# TAH_Relay_and_Sensor_Shield.net
KiCad netlist of a schematic drawn in EAGLE
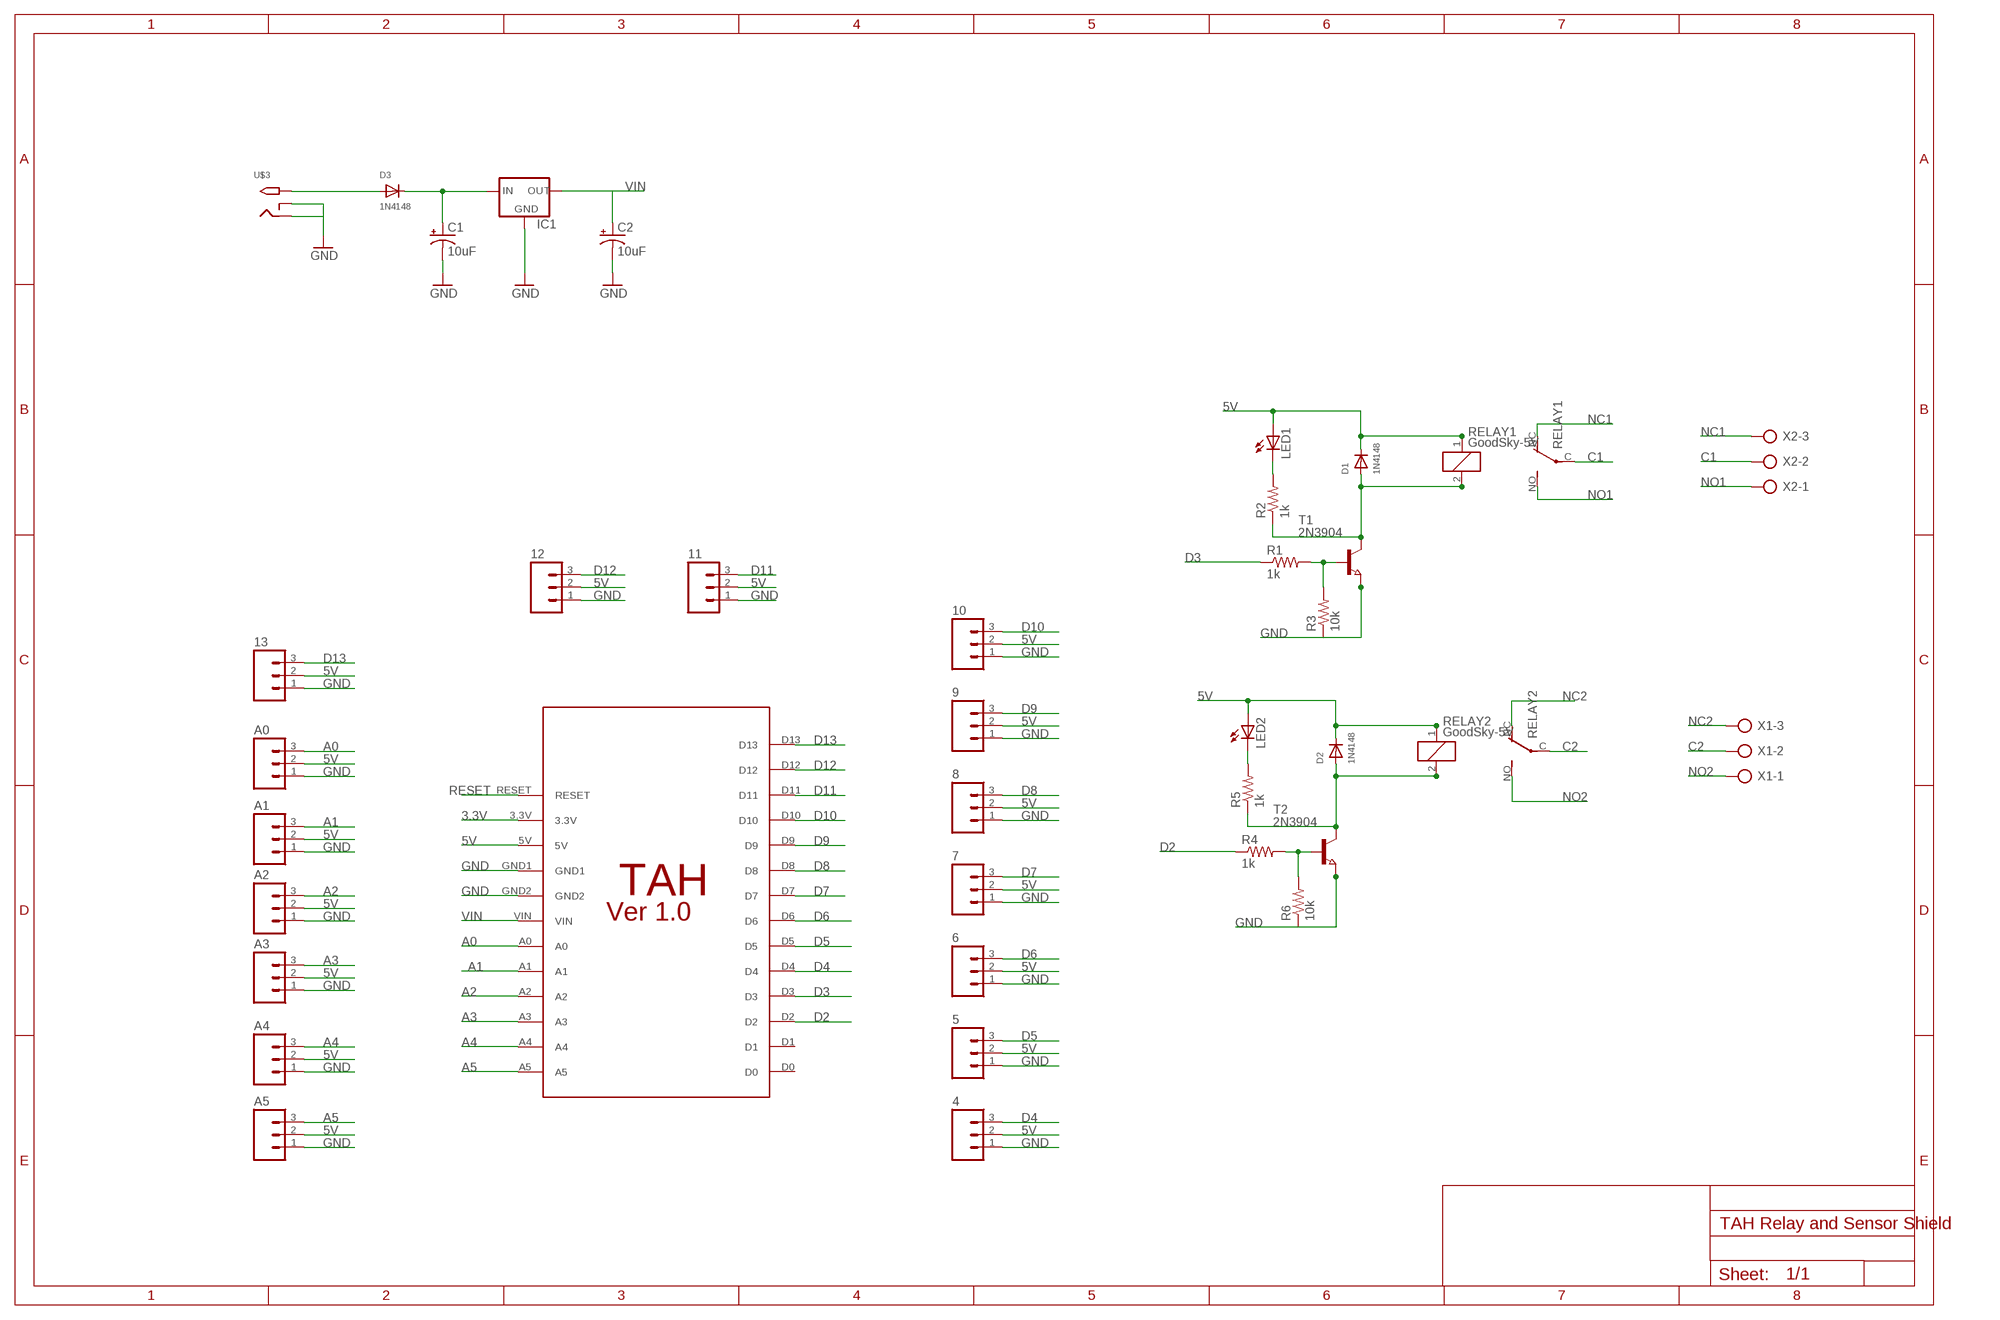
[diagram p0: schematic, sheet 1]

(export (version "E")
  (design (tool "Eeschema 10.0.6"))
  (components
    (comp (ref "4")
      (value "M03POLAR")
      (footprint "eagle-import:MOLEX-1X3")
      (libsource (lib "eagle-import") (part "M03POLAR"))
    )
    (comp (ref "5")
      (value "M03POLAR")
      (footprint "eagle-import:MOLEX-1X3")
      (libsource (lib "eagle-import") (part "M03POLAR"))
    )
    (comp (ref "6")
      (value "M03POLAR")
      (footprint "eagle-import:MOLEX-1X3")
      (libsource (lib "eagle-import") (part "M03POLAR"))
    )
    (comp (ref "7")
      (value "M03POLAR")
      (footprint "eagle-import:MOLEX-1X3")
      (libsource (lib "eagle-import") (part "M03POLAR"))
    )
    (comp (ref "8")
      (value "M03POLAR")
      (footprint "eagle-import:MOLEX-1X3")
      (libsource (lib "eagle-import") (part "M03POLAR"))
    )
    (comp (ref "9")
      (value "M03POLAR")
      (footprint "eagle-import:MOLEX-1X3")
      (libsource (lib "eagle-import") (part "M03POLAR"))
    )
    (comp (ref "10")
      (value "M03POLAR")
      (footprint "eagle-import:MOLEX-1X3")
      (libsource (lib "eagle-import") (part "M03POLAR"))
    )
    (comp (ref "11")
      (value "M03POLAR")
      (footprint "eagle-import:MOLEX-1X3")
      (libsource (lib "eagle-import") (part "M03POLAR"))
    )
    (comp (ref "12")
      (value "M03POLAR")
      (footprint "eagle-import:MOLEX-1X3")
      (libsource (lib "eagle-import") (part "M03POLAR"))
    )
    (comp (ref "13")
      (value "M03POLAR")
      (footprint "eagle-import:MOLEX-1X3")
      (libsource (lib "eagle-import") (part "M03POLAR"))
    )
    (comp (ref "A0")
      (value "M03POLAR")
      (footprint "eagle-import:MOLEX-1X3")
      (libsource (lib "eagle-import") (part "M03POLAR"))
    )
    (comp (ref "A1")
      (value "M03POLAR")
      (footprint "eagle-import:MOLEX-1X3")
      (libsource (lib "eagle-import") (part "M03POLAR"))
    )
    (comp (ref "A2")
      (value "M03POLAR")
      (footprint "eagle-import:MOLEX-1X3")
      (libsource (lib "eagle-import") (part "M03POLAR"))
    )
    (comp (ref "A3")
      (value "M03POLAR")
      (footprint "eagle-import:MOLEX-1X3")
      (libsource (lib "eagle-import") (part "M03POLAR"))
    )
    (comp (ref "A4")
      (value "M03POLAR")
      (footprint "eagle-import:MOLEX-1X3")
      (libsource (lib "eagle-import") (part "M03POLAR"))
    )
    (comp (ref "A5")
      (value "M03POLAR")
      (footprint "eagle-import:MOLEX-1X3")
      (libsource (lib "eagle-import") (part "M03POLAR"))
    )
    (comp (ref "C1")
      (value "10uF")
      (footprint "eagle-import:E2,5-6E")
      (libsource (lib "eagle-import") (part "CPOL-USE2,5-6E"))
    )
    (comp (ref "C2")
      (value "10uF")
      (footprint "eagle-import:E2,5-6E")
      (libsource (lib "eagle-import") (part "CPOL-USE2,5-6E"))
    )
    (comp (ref "D1")
      (value "1N4148")
      (footprint "eagle-import:SMADIODE")
      (libsource (lib "eagle-import") (part "DIODESMA"))
    )
    (comp (ref "D2")
      (value "1N4148")
      (footprint "eagle-import:SMADIODE")
      (libsource (lib "eagle-import") (part "DIODESMA"))
    )
    (comp (ref "D3")
      (value "1N4148")
      (footprint "eagle-import:SMADIODE")
      (libsource (lib "eagle-import") (part "DIODESMA"))
    )
    (comp (ref "IC1")
      (value "V_REG_78XX-TO-220")
      (footprint "eagle-import:TO-220-ALT")
      (libsource (lib "eagle-import") (part "V_REG_78XX-TO-220"))
    )
    (comp (ref "LED1")
      (value "LEDSMT1206")
      (footprint "eagle-import:1206")
      (libsource (lib "eagle-import") (part "LEDSMT1206"))
    )
    (comp (ref "LED2")
      (value "LEDSMT1206")
      (footprint "eagle-import:1206")
      (libsource (lib "eagle-import") (part "LEDSMT1206"))
    )
    (comp (ref "R1")
      (value "1k")
      (footprint "eagle-import:R1206")
      (libsource (lib "eagle-import") (part "R-US_R1206"))
    )
    (comp (ref "R2")
      (value "1k")
      (footprint "eagle-import:R1206")
      (libsource (lib "eagle-import") (part "R-US_R1206"))
    )
    (comp (ref "R3")
      (value "10k")
      (footprint "eagle-import:R1206")
      (libsource (lib "eagle-import") (part "R-US_R1206"))
    )
    (comp (ref "R4")
      (value "1k")
      (footprint "eagle-import:R1206")
      (libsource (lib "eagle-import") (part "R-US_R1206"))
    )
    (comp (ref "R5")
      (value "1k")
      (footprint "eagle-import:R1206")
      (libsource (lib "eagle-import") (part "R-US_R1206"))
    )
    (comp (ref "R6")
      (value "10k")
      (footprint "eagle-import:R1206")
      (libsource (lib "eagle-import") (part "R-US_R1206"))
    )
    (comp (ref "RELAY1")
      (value "GoodSky-5V")
      (footprint "eagle-import:CQ1")
      (libsource (lib "eagle-import") (part "CQ1-12V"))
    )
    (comp (ref "RELAY2")
      (value "GoodSky-5V")
      (footprint "eagle-import:CQ1")
      (libsource (lib "eagle-import") (part "CQ1-12V"))
    )
    (comp (ref "T1")
      (value "2N3904")
      (footprint "eagle-import:SOT23")
      (libsource (lib "eagle-import") (part "NPN-TRANSISTOR_SOT23"))
    )
    (comp (ref "T2")
      (value "2N3904")
      (footprint "eagle-import:SOT23")
      (libsource (lib "eagle-import") (part "NPN-TRANSISTOR_SOT23"))
    )
    (comp (ref "U$1")
      (value "TAH_PIN_FOOTPRINT_WITHOUT_ICSP_VER1.0")
      (footprint "eagle-import:FOOTPRINT_WITHOUT_ICSP")
      (libsource (lib "eagle-import") (part "TAH_PIN_FOOTPRINT_WITHOUT_ICSP_VER1.0"))
    )
    (comp (ref "U$3")
      (value "2.1MMJACKTHM")
      (footprint "eagle-import:PJ-102A")
      (libsource (lib "eagle-import") (part "2.1MMJACKTHM"))
    )
    (comp (ref "X1")
      (value "AK300/3")
      (footprint "eagle-import:AK300_3")
      (libsource (lib "eagle-import") (part "AK300/3"))
    )
    (comp (ref "X2")
      (value "AK300/3")
      (footprint "eagle-import:AK300_3")
      (libsource (lib "eagle-import") (part "AK300/3"))
    )
  )
  (nets
    (net (code "1") (name "/3.3V") (class "Default")
      (node (ref "U$1") (pin "3.3V") (pinfunction "3.3V_3.3V") (pintype "bidirectional"))
    )
    (net (code "2") (name "/5V") (class "Default")
      (node (ref "10") (pin "2") (pinfunction "2_2") (pintype "passive"))
      (node (ref "11") (pin "2") (pinfunction "2_2") (pintype "passive"))
      (node (ref "12") (pin "2") (pinfunction "2_2") (pintype "passive"))
      (node (ref "13") (pin "2") (pinfunction "2_2") (pintype "passive"))
      (node (ref "4") (pin "2") (pinfunction "2_2") (pintype "passive"))
      (node (ref "5") (pin "2") (pinfunction "2_2") (pintype "passive"))
      (node (ref "6") (pin "2") (pinfunction "2_2") (pintype "passive"))
      (node (ref "7") (pin "2") (pinfunction "2_2") (pintype "passive"))
      (node (ref "8") (pin "2") (pinfunction "2_2") (pintype "passive"))
      (node (ref "9") (pin "2") (pinfunction "2_2") (pintype "passive"))
      (node (ref "A0") (pin "2") (pinfunction "2_2") (pintype "passive"))
      (node (ref "A1") (pin "2") (pinfunction "2_2") (pintype "passive"))
      (node (ref "A2") (pin "2") (pinfunction "2_2") (pintype "passive"))
      (node (ref "A3") (pin "2") (pinfunction "2_2") (pintype "passive"))
      (node (ref "A4") (pin "2") (pinfunction "2_2") (pintype "passive"))
      (node (ref "A5") (pin "2") (pinfunction "2_2") (pintype "passive"))
      (node (ref "D1") (pin "C") (pinfunction "C_C") (pintype "passive"))
      (node (ref "D2") (pin "C") (pinfunction "C_C") (pintype "passive"))
      (node (ref "LED1") (pin "A") (pinfunction "A_A") (pintype "passive"))
      (node (ref "LED2") (pin "A") (pinfunction "A_A") (pintype "passive"))
      (node (ref "RELAY1") (pin "1") (pinfunction "1_1") (pintype "passive"))
      (node (ref "RELAY2") (pin "1") (pinfunction "1_1") (pintype "passive"))
      (node (ref "U$1") (pin "5V") (pinfunction "5V_5V") (pintype "bidirectional"))
    )
    (net (code "3") (name "/A0") (class "Default")
      (node (ref "A0") (pin "3") (pinfunction "3_3") (pintype "passive"))
      (node (ref "U$1") (pin "A0") (pinfunction "A0_A0") (pintype "bidirectional"))
    )
    (net (code "4") (name "/A1") (class "Default")
      (node (ref "A1") (pin "3") (pinfunction "3_3") (pintype "passive"))
      (node (ref "U$1") (pin "A1") (pinfunction "A1_A1") (pintype "bidirectional"))
    )
    (net (code "5") (name "/A2") (class "Default")
      (node (ref "A2") (pin "3") (pinfunction "3_3") (pintype "passive"))
      (node (ref "U$1") (pin "A2") (pinfunction "A2_A2") (pintype "bidirectional"))
    )
    (net (code "6") (name "/A3") (class "Default")
      (node (ref "A3") (pin "3") (pinfunction "3_3") (pintype "passive"))
      (node (ref "U$1") (pin "A3") (pinfunction "A3_A3") (pintype "bidirectional"))
    )
    (net (code "7") (name "/A4") (class "Default")
      (node (ref "A4") (pin "3") (pinfunction "3_3") (pintype "passive"))
      (node (ref "U$1") (pin "A4") (pinfunction "A4_A4") (pintype "bidirectional"))
    )
    (net (code "8") (name "/A5") (class "Default")
      (node (ref "A5") (pin "3") (pinfunction "3_3") (pintype "passive"))
      (node (ref "U$1") (pin "A5") (pinfunction "A5_A5") (pintype "bidirectional"))
    )
    (net (code "9") (name "/C1") (class "Default")
      (node (ref "RELAY1") (pin "C") (pinfunction "P_C") (pintype "passive"))
      (node (ref "X2") (pin "2") (pinfunction "KL_2") (pintype "passive"))
    )
    (net (code "10") (name "/C2") (class "Default")
      (node (ref "RELAY2") (pin "C") (pinfunction "P_C") (pintype "passive"))
      (node (ref "X1") (pin "2") (pinfunction "KL_2") (pintype "passive"))
    )
    (net (code "11") (name "/D2") (class "Default")
      (node (ref "R4") (pin "1") (pinfunction "1_1") (pintype "passive"))
      (node (ref "U$1") (pin "D2") (pinfunction "D2_D2") (pintype "bidirectional"))
    )
    (net (code "12") (name "/D3") (class "Default")
      (node (ref "R1") (pin "1") (pinfunction "1_1") (pintype "passive"))
      (node (ref "U$1") (pin "D3") (pinfunction "D3_D3") (pintype "bidirectional"))
    )
    (net (code "13") (name "/D4") (class "Default")
      (node (ref "4") (pin "3") (pinfunction "3_3") (pintype "passive"))
      (node (ref "U$1") (pin "D4") (pinfunction "D4_D4") (pintype "bidirectional"))
    )
    (net (code "14") (name "/D5") (class "Default")
      (node (ref "5") (pin "3") (pinfunction "3_3") (pintype "passive"))
      (node (ref "U$1") (pin "D5") (pinfunction "D5_D5") (pintype "bidirectional"))
    )
    (net (code "15") (name "/D6") (class "Default")
      (node (ref "6") (pin "3") (pinfunction "3_3") (pintype "passive"))
      (node (ref "U$1") (pin "D6") (pinfunction "D6_D6") (pintype "bidirectional"))
    )
    (net (code "16") (name "/D7") (class "Default")
      (node (ref "7") (pin "3") (pinfunction "3_3") (pintype "passive"))
      (node (ref "U$1") (pin "D7") (pinfunction "D7_D7") (pintype "bidirectional"))
    )
    (net (code "17") (name "/D8") (class "Default")
      (node (ref "8") (pin "3") (pinfunction "3_3") (pintype "passive"))
      (node (ref "U$1") (pin "D8") (pinfunction "D8_D8") (pintype "bidirectional"))
    )
    (net (code "18") (name "/D9") (class "Default")
      (node (ref "9") (pin "3") (pinfunction "3_3") (pintype "passive"))
      (node (ref "U$1") (pin "D9") (pinfunction "D9_D9") (pintype "bidirectional"))
    )
    (net (code "19") (name "/D10") (class "Default")
      (node (ref "10") (pin "3") (pinfunction "3_3") (pintype "passive"))
      (node (ref "U$1") (pin "D10") (pinfunction "D10_D10") (pintype "bidirectional"))
    )
    (net (code "20") (name "/D11") (class "Default")
      (node (ref "11") (pin "3") (pinfunction "3_3") (pintype "passive"))
      (node (ref "U$1") (pin "D11") (pinfunction "D11_D11") (pintype "bidirectional"))
    )
    (net (code "21") (name "/D12") (class "Default")
      (node (ref "12") (pin "3") (pinfunction "3_3") (pintype "passive"))
      (node (ref "U$1") (pin "D12") (pinfunction "D12_D12") (pintype "bidirectional"))
    )
    (net (code "22") (name "/D13") (class "Default")
      (node (ref "13") (pin "3") (pinfunction "3_3") (pintype "passive"))
      (node (ref "U$1") (pin "D13") (pinfunction "D13_D13") (pintype "bidirectional"))
    )
    (net (code "23") (name "/NC1") (class "Default")
      (node (ref "RELAY1") (pin "NC") (pinfunction "O_NC") (pintype "passive"))
      (node (ref "X2") (pin "3") (pinfunction "KL_3") (pintype "passive"))
    )
    (net (code "24") (name "/NC2") (class "Default")
      (node (ref "RELAY2") (pin "NC") (pinfunction "O_NC") (pintype "passive"))
      (node (ref "X1") (pin "3") (pinfunction "KL_3") (pintype "passive"))
    )
    (net (code "25") (name "/NO1") (class "Default")
      (node (ref "RELAY1") (pin "NO") (pinfunction "S_NO") (pintype "passive"))
      (node (ref "X2") (pin "1") (pinfunction "KL_1") (pintype "passive"))
    )
    (net (code "26") (name "/NO2") (class "Default")
      (node (ref "RELAY2") (pin "NO") (pinfunction "S_NO") (pintype "passive"))
      (node (ref "X1") (pin "1") (pinfunction "KL_1") (pintype "passive"))
    )
    (net (code "27") (name "/RESET") (class "Default")
      (node (ref "U$1") (pin "RESET") (pinfunction "RESET_RESET") (pintype "bidirectional"))
    )
    (net (code "28") (name "/VIN") (class "Default")
      (node (ref "C2") (pin "+") (pinfunction "+_+") (pintype "passive"))
      (node (ref "IC1") (pin "OUT") (pinfunction "OUT_OUT") (pintype "output"))
      (node (ref "U$1") (pin "VIN") (pinfunction "VIN_VIN") (pintype "bidirectional"))
    )
    (net (code "29") (name "GND") (class "Default")
      (node (ref "10") (pin "1") (pinfunction "1_1") (pintype "passive"))
      (node (ref "11") (pin "1") (pinfunction "1_1") (pintype "passive"))
      (node (ref "12") (pin "1") (pinfunction "1_1") (pintype "passive"))
      (node (ref "13") (pin "1") (pinfunction "1_1") (pintype "passive"))
      (node (ref "4") (pin "1") (pinfunction "1_1") (pintype "passive"))
      (node (ref "5") (pin "1") (pinfunction "1_1") (pintype "passive"))
      (node (ref "6") (pin "1") (pinfunction "1_1") (pintype "passive"))
      (node (ref "7") (pin "1") (pinfunction "1_1") (pintype "passive"))
      (node (ref "8") (pin "1") (pinfunction "1_1") (pintype "passive"))
      (node (ref "9") (pin "1") (pinfunction "1_1") (pintype "passive"))
      (node (ref "A0") (pin "1") (pinfunction "1_1") (pintype "passive"))
      (node (ref "A1") (pin "1") (pinfunction "1_1") (pintype "passive"))
      (node (ref "A2") (pin "1") (pinfunction "1_1") (pintype "passive"))
      (node (ref "A3") (pin "1") (pinfunction "1_1") (pintype "passive"))
      (node (ref "A4") (pin "1") (pinfunction "1_1") (pintype "passive"))
      (node (ref "A5") (pin "1") (pinfunction "1_1") (pintype "passive"))
      (node (ref "C1") (pin "-") (pinfunction "-_-") (pintype "passive"))
      (node (ref "C2") (pin "-") (pinfunction "-_-") (pintype "passive"))
      (node (ref "IC1") (pin "GND") (pinfunction "GND_GND") (pintype "input"))
      (node (ref "R3") (pin "1") (pinfunction "1_1") (pintype "passive"))
      (node (ref "R6") (pin "1") (pinfunction "1_1") (pintype "passive"))
      (node (ref "T1") (pin "2") (pinfunction "E_2") (pintype "passive"))
      (node (ref "T2") (pin "2") (pinfunction "E_2") (pintype "passive"))
      (node (ref "U$1") (pin "GND1") (pinfunction "GND1_GND1") (pintype "bidirectional"))
      (node (ref "U$1") (pin "GND2") (pinfunction "GND2_GND2") (pintype "bidirectional"))
      (node (ref "U$3") (pin "RING") (pinfunction "RING_RING") (pintype "bidirectional"))
      (node (ref "U$3") (pin "RING_SW") (pinfunction "RING_SW_RING_SW") (pintype "bidirectional"))
    )
    (net (code "30") (name "Net-(C1-Pad+)") (class "Default")
      (node (ref "C1") (pin "+") (pinfunction "+_+") (pintype "passive"))
      (node (ref "D3") (pin "C") (pinfunction "C_C") (pintype "passive"))
      (node (ref "IC1") (pin "IN") (pinfunction "IN_IN") (pintype "input"))
    )
    (net (code "31") (name "Net-(D3-PadA)") (class "Default")
      (node (ref "D3") (pin "A") (pinfunction "A_A") (pintype "passive"))
      (node (ref "U$3") (pin "TIP") (pinfunction "TIP_TIP") (pintype "bidirectional"))
    )
    (net (code "32") (name "Net-(LED1-PadC)") (class "Default")
      (node (ref "LED1") (pin "C") (pinfunction "C_C") (pintype "passive"))
      (node (ref "R2") (pin "2") (pinfunction "2_2") (pintype "passive"))
    )
    (net (code "33") (name "Net-(LED2-PadC)") (class "Default")
      (node (ref "LED2") (pin "C") (pinfunction "C_C") (pintype "passive"))
      (node (ref "R5") (pin "2") (pinfunction "2_2") (pintype "passive"))
    )
    (net (code "34") (name "Net-(T1-B)") (class "Default")
      (node (ref "R1") (pin "2") (pinfunction "2_2") (pintype "passive"))
      (node (ref "R3") (pin "2") (pinfunction "2_2") (pintype "passive"))
      (node (ref "T1") (pin "1") (pinfunction "B_1") (pintype "passive"))
    )
    (net (code "35") (name "Net-(T1-C)") (class "Default")
      (node (ref "D1") (pin "A") (pinfunction "A_A") (pintype "passive"))
      (node (ref "R2") (pin "1") (pinfunction "1_1") (pintype "passive"))
      (node (ref "RELAY1") (pin "2") (pinfunction "2_2") (pintype "passive"))
      (node (ref "T1") (pin "3") (pinfunction "C_3") (pintype "passive"))
    )
    (net (code "36") (name "Net-(T2-B)") (class "Default")
      (node (ref "R4") (pin "2") (pinfunction "2_2") (pintype "passive"))
      (node (ref "R6") (pin "2") (pinfunction "2_2") (pintype "passive"))
      (node (ref "T2") (pin "1") (pinfunction "B_1") (pintype "passive"))
    )
    (net (code "37") (name "Net-(T2-C)") (class "Default")
      (node (ref "D2") (pin "A") (pinfunction "A_A") (pintype "passive"))
      (node (ref "R5") (pin "1") (pinfunction "1_1") (pintype "passive"))
      (node (ref "RELAY2") (pin "2") (pinfunction "2_2") (pintype "passive"))
      (node (ref "T2") (pin "3") (pinfunction "C_3") (pintype "passive"))
    )
    (net (code "38") (name "unconnected-(U$1-PadD0)") (class "Default")
      (node (ref "U$1") (pin "D0") (pinfunction "D0_D0") (pintype "bidirectional"))
    )
    (net (code "39") (name "unconnected-(U$1-PadD1)") (class "Default")
      (node (ref "U$1") (pin "D1") (pinfunction "D1_D1") (pintype "bidirectional"))
    )
  )
)
